# PG03_Schematic_Sheet1.net
KiCad netlist of a schematic drawn in Altium Designer
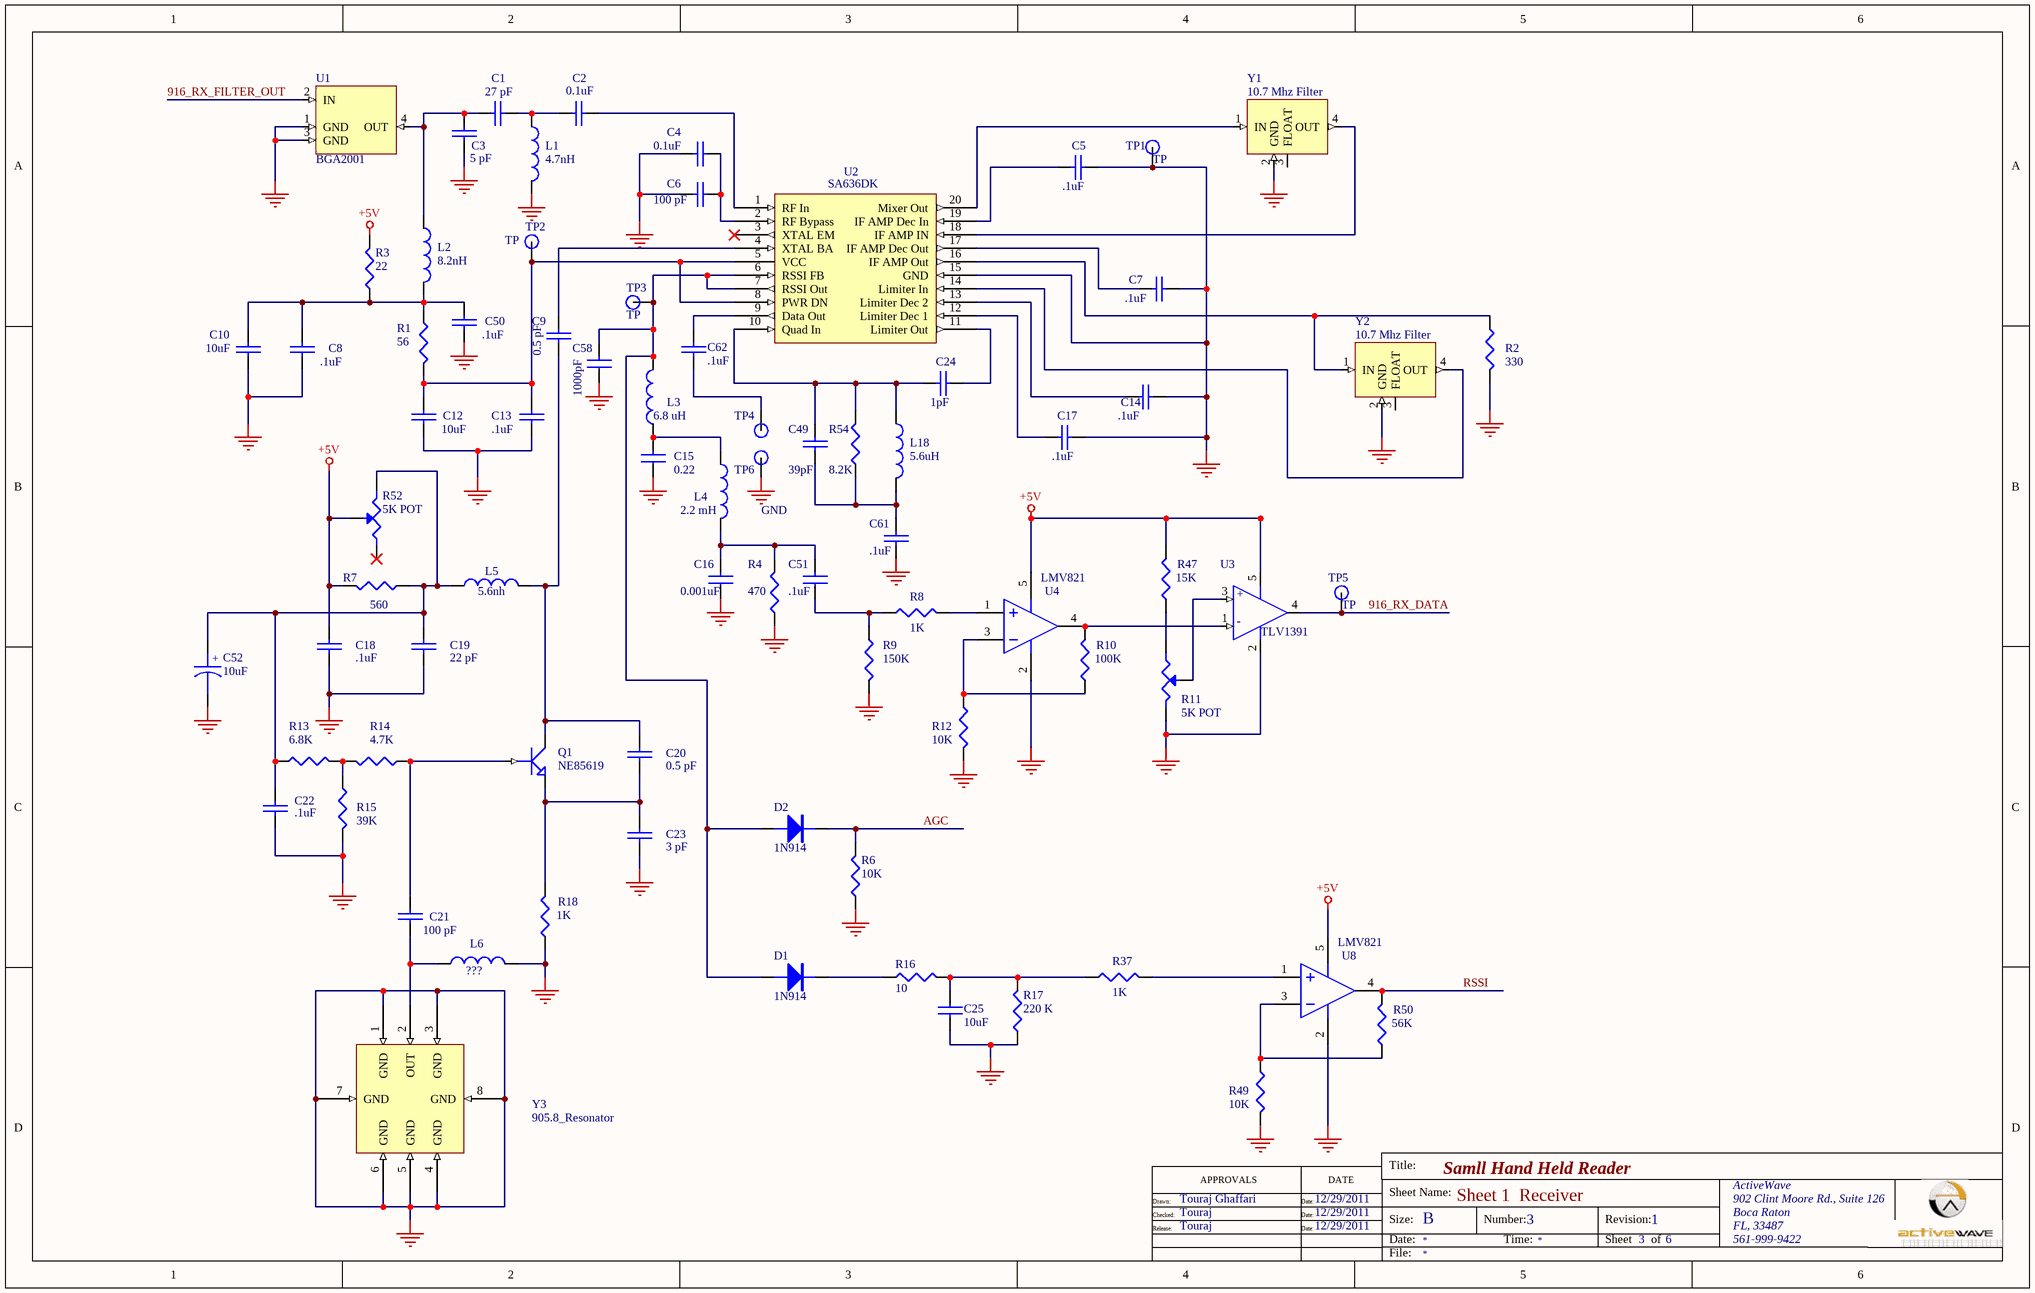
[diagram p0: PG03_Schematic Sheet1.SchDoc]

(export (version "E")
  (design (tool "Eeschema 10.0.6"))
  (components
    (comp (ref "C1")
      (value "27 pF")
      (footprint "0603")
      (description "Capacitor")
      (libsource (lib "*") (part "CAP"))
    )
    (comp (ref "C2")
      (value "0.1uF")
      (footprint "0603")
      (description "Capacitor")
      (libsource (lib "*") (part "CAP"))
    )
    (comp (ref "C3")
      (value "5 pF")
      (footprint "0603")
      (description "Capacitor")
      (libsource (lib "*") (part "CAP"))
    )
    (comp (ref "C4")
      (value "0.1uF")
      (footprint "0603")
      (description "Capacitor")
      (libsource (lib "*") (part "CAP"))
    )
    (comp (ref "C5")
      (value ".1uF")
      (footprint "0603")
      (description "Capacitor")
      (libsource (lib "*") (part "CAP"))
    )
    (comp (ref "C6")
      (value "100 pF")
      (footprint "0603")
      (description "Capacitor")
      (libsource (lib "*") (part "CAP"))
    )
    (comp (ref "C7")
      (value ".1uF")
      (footprint "0603")
      (description "Capacitor")
      (libsource (lib "*") (part "CAP"))
    )
    (comp (ref "C8")
      (value ".1uF")
      (footprint "0603")
      (description "Capacitor")
      (libsource (lib "*") (part "CAP"))
    )
    (comp (ref "C9")
      (value "0.5 pF")
      (footprint "0603")
      (description "Capacitor")
      (libsource (lib "*") (part "CAP"))
    )
    (comp (ref "C10")
      (value "10uF")
      (footprint "CAP A CASE")
      (description "Capacitor")
      (libsource (lib "*") (part "CAP"))
    )
    (comp (ref "C12")
      (value "10uF")
      (footprint "CAP A CASE")
      (description "Capacitor")
      (libsource (lib "*") (part "CAP"))
    )
    (comp (ref "C13")
      (value ".1uF")
      (footprint "0603")
      (description "Capacitor")
      (libsource (lib "*") (part "CAP"))
    )
    (comp (ref "C14")
      (value ".1uF")
      (footprint "0603")
      (description "Capacitor")
      (libsource (lib "*") (part "CAP"))
    )
    (comp (ref "C15") (value "0.22") (footprint "0603") (libsource (lib "*") (part "CAP_NP")))
    (comp (ref "C16") (value "0.001uF") (footprint "0603") (libsource (lib "*") (part "CAP_NP")))
    (comp (ref "C17")
      (value ".1uF")
      (footprint "0603")
      (description "Capacitor")
      (libsource (lib "*") (part "CAP"))
    )
    (comp (ref "C18")
      (value ".1uF")
      (footprint "0603")
      (description "Capacitor")
      (libsource (lib "*") (part "CAP"))
    )
    (comp (ref "C19")
      (value "22 pF")
      (footprint "0603")
      (description "Capacitor")
      (libsource (lib "*") (part "CAP"))
    )
    (comp (ref "C20")
      (value "0.5 pF")
      (footprint "0603")
      (description "Capacitor")
      (libsource (lib "*") (part "CAP"))
    )
    (comp (ref "C21")
      (value "100 pF")
      (footprint "0603")
      (description "Capacitor")
      (libsource (lib "*") (part "CAP"))
    )
    (comp (ref "C22")
      (value ".1uF")
      (footprint "0603")
      (description "Capacitor")
      (libsource (lib "*") (part "CAP"))
    )
    (comp (ref "C23")
      (value "3 pF")
      (footprint "0603")
      (description "Capacitor")
      (libsource (lib "*") (part "CAP"))
    )
    (comp (ref "C24")
      (value "1pF")
      (footprint "0603")
      (description "Capacitor")
      (libsource (lib "*") (part "CAP"))
    )
    (comp (ref "C25") (value "10uF") (footprint "CAP A CASE") (libsource (lib "*") (part "CAP_NP")))
    (comp (ref "C49")
      (value "39pF")
      (footprint "0603")
      (description "Capacitor")
      (libsource (lib "*") (part "CAP"))
    )
    (comp (ref "C50")
      (value ".1uF")
      (footprint "0603")
      (description "Capacitor")
      (libsource (lib "*") (part "CAP"))
    )
    (comp (ref "C51") (value ".1uF") (footprint "0603") (libsource (lib "*") (part "CAP_NP")))
    (comp (ref "C52")
      (value "10uF")
      (footprint "CAP A CASE")
      (description "Capacitor")
      (libsource (lib "*") (part "CAPACITOR POL"))
    )
    (comp (ref "C58") (value "1000pF") (footprint "0603") (libsource (lib "*") (part "CAP_NP")))
    (comp (ref "C61")
      (value ".1uF")
      (footprint "0603")
      (description "Capacitor")
      (libsource (lib "*") (part "CAP"))
    )
    (comp (ref "C62")
      (value ".1uF")
      (footprint "0603")
      (description "Capacitor")
      (libsource (lib "*") (part "CAP"))
    )
    (comp (ref "D1")
      (value "1N914")
      (footprint "SOT23 DIODE")
      (description "Diode")
      (libsource (lib "*") (part "DIODE"))
    )
    (comp (ref "D2")
      (value "1N914")
      (footprint "SOT23 DIODE")
      (description "Diode")
      (libsource (lib "*") (part "DIODE"))
    )
    (comp (ref "L1") (value "4.7nH") (footprint "0603") (libsource (lib "*") (part "INDUCTOR")))
    (comp (ref "L2") (value "8.2nH") (footprint "0603") (libsource (lib "*") (part "INDUCTOR")))
    (comp (ref "L3") (value "6.8 uH") (footprint "0805") (libsource (lib "*") (part "INDUCTOR")))
    (comp (ref "L4") (value "2.2 mH") (footprint "COIL TKS5540CT-ND") (libsource (lib "*") (part "INDUCTOR")))
    (comp (ref "L5") (value "5.6nh") (footprint "0603") (libsource (lib "*") (part "INDUCTOR")))
    (comp (ref "L6") (value "???") (footprint "0603") (libsource (lib "*") (part "INDUCTOR")))
    (comp (ref "L18") (value "5.6uH") (footprint "0603") (libsource (lib "*") (part "INDUCTOR")))
    (comp (ref "Q1")
      (value "NE85619")
      (footprint "3 PIN ULTRA SUPER MINI MOLD")
      (description "NPN Transistor")
      (libsource (lib "*") (part "NPN1"))
    )
    (comp (ref "R1") (value "56") (footprint "0603") (libsource (lib "*") (part "R")))
    (comp (ref "R2") (value "330") (footprint "0603") (libsource (lib "*") (part "R")))
    (comp (ref "R3") (value "22") (footprint "0603") (libsource (lib "*") (part "R")))
    (comp (ref "R4") (value "470") (footprint "0603") (libsource (lib "*") (part "R")))
    (comp (ref "R6") (value "10K") (footprint "0603") (libsource (lib "*") (part "R")))
    (comp (ref "R7") (value "560") (footprint "0603") (libsource (lib "*") (part "RESISTOR")))
    (comp (ref "R8") (value "1K") (footprint "0603") (libsource (lib "*") (part "R")))
    (comp (ref "R9") (value "150K") (footprint "0603") (libsource (lib "*") (part "R")))
    (comp (ref "R10") (value "100K") (footprint "0603") (libsource (lib "*") (part "R")))
    (comp (ref "R11")
      (value "5K POT")
      (footprint "POT PANA EVN5")
      (description "Potentiometer")
      (libsource (lib "*") (part "POT1"))
    )
    (comp (ref "R12") (value "10K") (footprint "0603") (libsource (lib "*") (part "R")))
    (comp (ref "R13") (value "6.8K") (footprint "0603") (libsource (lib "*") (part "RESISTOR")))
    (comp (ref "R14") (value "4.7K") (footprint "0603") (libsource (lib "*") (part "RESISTOR")))
    (comp (ref "R15") (value "39K") (footprint "0603") (libsource (lib "*") (part "RESISTOR")))
    (comp (ref "R16") (value "10") (footprint "0603") (libsource (lib "*") (part "R")))
    (comp (ref "R17") (value "220 K") (footprint "0603") (libsource (lib "*") (part "R")))
    (comp (ref "R18") (value "1K") (footprint "0603") (libsource (lib "*") (part "RESISTOR")))
    (comp (ref "R37") (value "1K") (footprint "0603") (libsource (lib "*") (part "R")))
    (comp (ref "R47") (value "15K") (footprint "0603") (libsource (lib "*") (part "R")))
    (comp (ref "R49") (value "10K") (footprint "0603") (libsource (lib "*") (part "R")))
    (comp (ref "R50") (value "56K") (footprint "0603") (libsource (lib "*") (part "R")))
    (comp (ref "R52")
      (value "5K POT")
      (footprint "POT PANA EVN5")
      (description "Potentiometer")
      (libsource (lib "") (part "POT1_1"))
    )
    (comp (ref "R54") (value "8.2K") (footprint "0603") (libsource (lib "*") (part "R")))
    (comp (ref "TP1") (value "TP") (footprint "TESTPOINT") (libsource (lib "TRX-101R16") (part "TP")))
    (comp (ref "TP2") (value "TP") (footprint "TESTPOINT") (libsource (lib "TRX-101R16") (part "TP")))
    (comp (ref "TP3") (value "TP") (footprint "TESTPOINT") (libsource (lib "TRX-101R16") (part "TP")))
    (comp (ref "TP4") (value "TP") (footprint "TESTPOINT") (libsource (lib "TRX-101R16") (part "TP")))
    (comp (ref "TP5") (value "TP") (footprint "TESTPOINT") (libsource (lib "TRX-101R16") (part "TP")))
    (comp (ref "TP6") (value "GND") (footprint "TESTPOINT") (libsource (lib "TRX-101R16") (part "TP")))
    (comp (ref "U1") (value "BGA2001") (footprint "SOT343") (libsource (lib "*") (part "BGA2001")))
    (comp (ref "U2") (value "SA636DK") (footprint "SSOP20") (libsource (lib "*") (part "SA636DK")))
    (comp (ref "U3") (value "TLV1391") (footprint "SOT25") (libsource (lib "*") (part "TLV1391")))
    (comp (ref "U4") (value "LMV821") (footprint "SOT25") (libsource (lib "*") (part "OPAMP1")))
    (comp (ref "U8") (value "LMV821") (footprint "SOT25") (libsource (lib "*") (part "OPAMP1")))
    (comp (ref "Y1") (value "10.7 Mhz Filter") (footprint "FILTER2") (libsource (lib "*") (part "FILTER2")))
    (comp (ref "Y2") (value "10.7 Mhz Filter") (footprint "FILTER2") (libsource (lib "*") (part "FILTER2")))
    (comp (ref "Y3")
      (value "905.8_Resonator")
      (footprint "RESONATOR")
      (libsource (lib "TRX-101_16") (part "RESONATOR2"))
    )
  )
  (nets
    (net (code "1") (name "+5V") (class "Default")
      (node (ref "C18") (pin "1") (pinfunction "1_1") (pintype "passive"))
      (node (ref "R3") (pin "2") (pinfunction "2_2") (pintype "passive"))
      (node (ref "R47") (pin "2") (pinfunction "2_2") (pintype "passive"))
      (node (ref "R52") (pin "2") (pinfunction "2_2") (pintype "passive"))
      (node (ref "R7") (pin "2") (pinfunction "2_2") (pintype "passive"))
      (node (ref "U3") (pin "5") (pinfunction "VDD_5") (pintype "power_in"))
      (node (ref "U4") (pin "5") (pinfunction "5_5") (pintype "passive"))
      (node (ref "U8") (pin "5") (pinfunction "5_5") (pintype "passive"))
    )
    (net (code "2") (name "/916_RX_DATA") (class "Default")
      (node (ref "TP5") (pin "1") (pinfunction "TP_1") (pintype "passive"))
      (node (ref "U3") (pin "4") (pinfunction "OUT_4") (pintype "open_collector"))
    )
    (net (code "3") (name "/916_RX_FILTER_OUT") (class "Default")
      (node (ref "U1") (pin "2") (pinfunction "IN_2") (pintype "input"))
    )
    (net (code "4") (name "/AGC") (class "Default")
      (node (ref "D2") (pin "K") (pinfunction "K_K") (pintype "passive"))
      (node (ref "R6") (pin "1") (pinfunction "1_1") (pintype "passive"))
    )
    (net (code "5") (name "/RSSI") (class "Default")
      (node (ref "R50") (pin "2") (pinfunction "2_2") (pintype "passive"))
      (node (ref "U8") (pin "4") (pinfunction "4_4") (pintype "passive"))
    )
    (net (code "6") (name "GND_SIGNAL") (class "Default")
      (node (ref "C10") (pin "2") (pinfunction "2_2") (pintype "passive"))
      (node (ref "C12") (pin "2") (pinfunction "2_2") (pintype "passive"))
      (node (ref "C13") (pin "2") (pinfunction "2_2") (pintype "passive"))
      (node (ref "C14") (pin "2") (pinfunction "2_2") (pintype "passive"))
      (node (ref "C15") (pin "1") (pinfunction "1_1") (pintype "passive"))
      (node (ref "C16") (pin "1") (pinfunction "1_1") (pintype "passive"))
      (node (ref "C17") (pin "2") (pinfunction "2_2") (pintype "passive"))
      (node (ref "C18") (pin "2") (pinfunction "2_2") (pintype "passive"))
      (node (ref "C19") (pin "2") (pinfunction "2_2") (pintype "passive"))
      (node (ref "C22") (pin "2") (pinfunction "2_2") (pintype "passive"))
      (node (ref "C23") (pin "2") (pinfunction "2_2") (pintype "passive"))
      (node (ref "C25") (pin "2") (pinfunction "2_2") (pintype "passive"))
      (node (ref "C3") (pin "2") (pinfunction "2_2") (pintype "passive"))
      (node (ref "C4") (pin "1") (pinfunction "1_1") (pintype "passive"))
      (node (ref "C5") (pin "2") (pinfunction "2_2") (pintype "passive"))
      (node (ref "C50") (pin "2") (pinfunction "2_2") (pintype "passive"))
      (node (ref "C52") (pin "2") (pinfunction "2_2") (pintype "passive"))
      (node (ref "C58") (pin "1") (pinfunction "1_1") (pintype "passive"))
      (node (ref "C6") (pin "1") (pinfunction "1_1") (pintype "passive"))
      (node (ref "C61") (pin "2") (pinfunction "2_2") (pintype "passive"))
      (node (ref "C7") (pin "2") (pinfunction "2_2") (pintype "passive"))
      (node (ref "C8") (pin "2") (pinfunction "2_2") (pintype "passive"))
      (node (ref "L1") (pin "2") (pinfunction "2_2") (pintype "passive"))
      (node (ref "L6") (pin "2") (pinfunction "2_2") (pintype "passive"))
      (node (ref "R11") (pin "3") (pinfunction "3_3") (pintype "passive"))
      (node (ref "R12") (pin "2") (pinfunction "2_2") (pintype "passive"))
      (node (ref "R15") (pin "2") (pinfunction "2_2") (pintype "passive"))
      (node (ref "R17") (pin "2") (pinfunction "2_2") (pintype "passive"))
      (node (ref "R18") (pin "1") (pinfunction "1_1") (pintype "passive"))
      (node (ref "R2") (pin "2") (pinfunction "2_2") (pintype "passive"))
      (node (ref "R4") (pin "1") (pinfunction "1_1") (pintype "passive"))
      (node (ref "R49") (pin "2") (pinfunction "2_2") (pintype "passive"))
      (node (ref "R6") (pin "2") (pinfunction "2_2") (pintype "passive"))
      (node (ref "R9") (pin "2") (pinfunction "2_2") (pintype "passive"))
      (node (ref "TP1") (pin "1") (pinfunction "TP_1") (pintype "passive"))
      (node (ref "TP6") (pin "1") (pinfunction "TP_1") (pintype "passive"))
      (node (ref "U1") (pin "1") (pinfunction "GND_1") (pintype "input"))
      (node (ref "U1") (pin "3") (pinfunction "GND_3") (pintype "input"))
      (node (ref "U2") (pin "15") (pinfunction "GND_15") (pintype "input"))
      (node (ref "U3") (pin "2") (pinfunction "VSS_2") (pintype "power_in"))
      (node (ref "U4") (pin "2") (pinfunction "2_2") (pintype "passive"))
      (node (ref "U8") (pin "2") (pinfunction "2_2") (pintype "passive"))
      (node (ref "Y1") (pin "2") (pinfunction "GND_2") (pintype "input"))
      (node (ref "Y2") (pin "2") (pinfunction "GND_2") (pintype "input"))
      (node (ref "Y3") (pin "1") (pinfunction "GND_1") (pintype "input"))
      (node (ref "Y3") (pin "3") (pinfunction "GND_3") (pintype "input"))
      (node (ref "Y3") (pin "4") (pinfunction "GND_4") (pintype "input"))
      (node (ref "Y3") (pin "5") (pinfunction "GND_5") (pintype "input"))
      (node (ref "Y3") (pin "6") (pinfunction "GND_6") (pintype "input"))
      (node (ref "Y3") (pin "7") (pinfunction "GND_7") (pintype "input"))
      (node (ref "Y3") (pin "8") (pinfunction "GND_8") (pintype "input"))
    )
    (net (code "7") (name "Net-(C1-Pad2)") (class "Default")
      (node (ref "C1") (pin "2") (pinfunction "2_2") (pintype "passive"))
      (node (ref "C2") (pin "1") (pinfunction "1_1") (pintype "passive"))
      (node (ref "L1") (pin "1") (pinfunction "1_1") (pintype "passive"))
    )
    (net (code "8") (name "Net-(C10-Pad1)") (class "Default")
      (node (ref "C10") (pin "1") (pinfunction "1_1") (pintype "passive"))
      (node (ref "C50") (pin "1") (pinfunction "1_1") (pintype "passive"))
      (node (ref "C8") (pin "1") (pinfunction "1_1") (pintype "passive"))
      (node (ref "L2") (pin "2") (pinfunction "2_2") (pintype "passive"))
      (node (ref "R1") (pin "1") (pinfunction "1_1") (pintype "passive"))
      (node (ref "R3") (pin "1") (pinfunction "1_1") (pintype "passive"))
    )
    (net (code "9") (name "Net-(C15-Pad2)") (class "Default")
      (node (ref "C15") (pin "2") (pinfunction "2_2") (pintype "passive"))
      (node (ref "L3") (pin "1") (pinfunction "1_1") (pintype "passive"))
      (node (ref "L4") (pin "1") (pinfunction "1_1") (pintype "passive"))
    )
    (net (code "10") (name "Net-(C16-Pad2)") (class "Default")
      (node (ref "C16") (pin "2") (pinfunction "2_2") (pintype "passive"))
      (node (ref "C51") (pin "2") (pinfunction "2_2") (pintype "passive"))
      (node (ref "L4") (pin "2") (pinfunction "2_2") (pintype "passive"))
      (node (ref "R4") (pin "2") (pinfunction "2_2") (pintype "passive"))
    )
    (net (code "11") (name "Net-(C19-Pad1)") (class "Default")
      (node (ref "C19") (pin "1") (pinfunction "1_1") (pintype "passive"))
      (node (ref "C22") (pin "1") (pinfunction "1_1") (pintype "passive"))
      (node (ref "C52") (pin "1") (pinfunction "1_1") (pintype "passive"))
      (node (ref "L5") (pin "1") (pinfunction "1_1") (pintype "passive"))
      (node (ref "R13") (pin "1") (pinfunction "1_1") (pintype "passive"))
      (node (ref "R52") (pin "1") (pinfunction "1_1") (pintype "passive"))
      (node (ref "R7") (pin "1") (pinfunction "1_1") (pintype "passive"))
    )
    (net (code "12") (name "Net-(C20-Pad1)") (class "Default")
      (node (ref "C20") (pin "1") (pinfunction "1_1") (pintype "passive"))
      (node (ref "C9") (pin "1") (pinfunction "1_1") (pintype "passive"))
      (node (ref "L5") (pin "2") (pinfunction "2_2") (pintype "passive"))
      (node (ref "Q1") (pin "C") (pinfunction "C_C") (pintype "passive"))
    )
    (net (code "13") (name "Net-(C20-Pad2)") (class "Default")
      (node (ref "C20") (pin "2") (pinfunction "2_2") (pintype "passive"))
      (node (ref "C23") (pin "1") (pinfunction "1_1") (pintype "passive"))
      (node (ref "Q1") (pin "E") (pinfunction "E_E") (pintype "passive"))
      (node (ref "R18") (pin "2") (pinfunction "2_2") (pintype "passive"))
    )
    (net (code "14") (name "Net-(C21-Pad1)") (class "Default")
      (node (ref "C21") (pin "1") (pinfunction "1_1") (pintype "passive"))
      (node (ref "Q1") (pin "B") (pinfunction "B_B") (pintype "input"))
      (node (ref "R14") (pin "1") (pinfunction "1_1") (pintype "passive"))
    )
    (net (code "15") (name "Net-(C25-Pad1)") (class "Default")
      (node (ref "C25") (pin "1") (pinfunction "1_1") (pintype "passive"))
      (node (ref "R16") (pin "1") (pinfunction "1_1") (pintype "passive"))
      (node (ref "R17") (pin "1") (pinfunction "1_1") (pintype "passive"))
      (node (ref "R37") (pin "1") (pinfunction "1_1") (pintype "passive"))
    )
    (net (code "16") (name "Net-(C49-Pad2)") (class "Default")
      (node (ref "C49") (pin "2") (pinfunction "2_2") (pintype "passive"))
      (node (ref "C61") (pin "1") (pinfunction "1_1") (pintype "passive"))
      (node (ref "L18") (pin "2") (pinfunction "2_2") (pintype "passive"))
      (node (ref "R54") (pin "1") (pinfunction "1_1") (pintype "passive"))
    )
    (net (code "17") (name "Net-(C51-Pad1)") (class "Default")
      (node (ref "C51") (pin "1") (pinfunction "1_1") (pintype "passive"))
      (node (ref "R8") (pin "1") (pinfunction "1_1") (pintype "passive"))
      (node (ref "R9") (pin "1") (pinfunction "1_1") (pintype "passive"))
    )
    (net (code "18") (name "Net-(D1-PadK)") (class "Default")
      (node (ref "D1") (pin "K") (pinfunction "K_K") (pintype "passive"))
      (node (ref "R16") (pin "2") (pinfunction "2_2") (pintype "passive"))
    )
    (net (code "19") (name "Net-(R8-Pad2)") (class "Default")
      (node (ref "R8") (pin "2") (pinfunction "2_2") (pintype "passive"))
      (node (ref "U4") (pin "1") (pinfunction "1_1") (pintype "passive"))
    )
    (net (code "20") (name "Net-(R10-Pad1)") (class "Default")
      (node (ref "R10") (pin "1") (pinfunction "1_1") (pintype "passive"))
      (node (ref "R12") (pin "1") (pinfunction "1_1") (pintype "passive"))
      (node (ref "U4") (pin "3") (pinfunction "3_3") (pintype "passive"))
    )
    (net (code "21") (name "Net-(R11-Pad1)") (class "Default")
      (node (ref "R11") (pin "1") (pinfunction "1_1") (pintype "passive"))
      (node (ref "R47") (pin "1") (pinfunction "1_1") (pintype "passive"))
    )
    (net (code "22") (name "Net-(R13-Pad2)") (class "Default")
      (node (ref "R13") (pin "2") (pinfunction "2_2") (pintype "passive"))
      (node (ref "R14") (pin "2") (pinfunction "2_2") (pintype "passive"))
      (node (ref "R15") (pin "1") (pinfunction "1_1") (pintype "passive"))
    )
    (net (code "23") (name "Net-(R37-Pad2)") (class "Default")
      (node (ref "R37") (pin "2") (pinfunction "2_2") (pintype "passive"))
      (node (ref "U8") (pin "1") (pinfunction "1_1") (pintype "passive"))
    )
    (net (code "24") (name "Net-(R49-Pad1)") (class "Default")
      (node (ref "R49") (pin "1") (pinfunction "1_1") (pintype "passive"))
      (node (ref "R50") (pin "1") (pinfunction "1_1") (pintype "passive"))
      (node (ref "U8") (pin "3") (pinfunction "3_3") (pintype "passive"))
    )
    (net (code "25") (name "Net-(TP2-TP)") (class "Default")
      (node (ref "C12") (pin "1") (pinfunction "1_1") (pintype "passive"))
      (node (ref "C13") (pin "1") (pinfunction "1_1") (pintype "passive"))
      (node (ref "R1") (pin "2") (pinfunction "2_2") (pintype "passive"))
      (node (ref "TP2") (pin "1") (pinfunction "TP_1") (pintype "passive"))
      (node (ref "U2") (pin "5") (pinfunction "VCC_5") (pintype "power_in"))
      (node (ref "U2") (pin "8") (pinfunction "PWR_DN_8") (pintype "input"))
    )
    (net (code "26") (name "Net-(TP3-TP)") (class "Default")
      (node (ref "C58") (pin "2") (pinfunction "2_2") (pintype "passive"))
      (node (ref "D1") (pin "A") (pinfunction "A_A") (pintype "passive"))
      (node (ref "D2") (pin "A") (pinfunction "A_A") (pintype "passive"))
      (node (ref "L3") (pin "2") (pinfunction "2_2") (pintype "passive"))
      (node (ref "TP3") (pin "1") (pinfunction "TP_1") (pintype "passive"))
      (node (ref "U2") (pin "6") (pinfunction "RSSI_FB_6") (pintype "input"))
      (node (ref "U2") (pin "7") (pinfunction "RSSI_Out_7") (pintype "output"))
    )
    (net (code "27") (name "Net-(TP4-TP)") (class "Default")
      (node (ref "C62") (pin "1") (pinfunction "1_1") (pintype "passive"))
      (node (ref "TP4") (pin "1") (pinfunction "TP_1") (pintype "passive"))
    )
    (net (code "28") (name "Net-(U1-OUT)") (class "Default")
      (node (ref "C1") (pin "1") (pinfunction "1_1") (pintype "passive"))
      (node (ref "C3") (pin "1") (pinfunction "1_1") (pintype "passive"))
      (node (ref "L2") (pin "1") (pinfunction "1_1") (pintype "passive"))
      (node (ref "U1") (pin "4") (pinfunction "OUT_4") (pintype "input"))
    )
    (net (code "29") (name "Net-(U2-Data_Out)") (class "Default")
      (node (ref "C62") (pin "2") (pinfunction "2_2") (pintype "passive"))
      (node (ref "U2") (pin "9") (pinfunction "Data_Out_9") (pintype "output"))
    )
    (net (code "30") (name "Net-(U2-IF_AMP_Dec_In)") (class "Default")
      (node (ref "C5") (pin "1") (pinfunction "1_1") (pintype "passive"))
      (node (ref "U2") (pin "19") (pinfunction "IF_AMP_Dec_In_19") (pintype "input"))
    )
    (net (code "31") (name "Net-(U2-IF_AMP_Dec_Out)") (class "Default")
      (node (ref "C7") (pin "1") (pinfunction "1_1") (pintype "passive"))
      (node (ref "U2") (pin "17") (pinfunction "IF_AMP_Dec_Out_17") (pintype "output"))
    )
    (net (code "32") (name "Net-(U2-IF_AMP_IN)") (class "Default")
      (node (ref "U2") (pin "18") (pinfunction "IF_AMP_IN_18") (pintype "input"))
      (node (ref "Y1") (pin "4") (pinfunction "OUT_4") (pintype "output"))
    )
    (net (code "33") (name "Net-(U2-IF_AMP_Out)") (class "Default")
      (node (ref "R2") (pin "1") (pinfunction "1_1") (pintype "passive"))
      (node (ref "U2") (pin "16") (pinfunction "IF_AMP_Out_16") (pintype "output"))
      (node (ref "Y2") (pin "1") (pinfunction "IN_1") (pintype "input"))
    )
    (net (code "34") (name "Net-(U2-Limiter_Dec_1)") (class "Default")
      (node (ref "C17") (pin "1") (pinfunction "1_1") (pintype "passive"))
      (node (ref "U2") (pin "12") (pinfunction "Limiter_Dec_1_12") (pintype "input"))
    )
    (net (code "35") (name "Net-(U2-Limiter_Dec_2)") (class "Default")
      (node (ref "C14") (pin "1") (pinfunction "1_1") (pintype "passive"))
      (node (ref "U2") (pin "13") (pinfunction "Limiter_Dec_2_13") (pintype "input"))
    )
    (net (code "36") (name "Net-(U2-Limiter_In)") (class "Default")
      (node (ref "U2") (pin "14") (pinfunction "Limiter_In_14") (pintype "input"))
      (node (ref "Y2") (pin "4") (pinfunction "OUT_4") (pintype "output"))
    )
    (net (code "37") (name "Net-(U2-Limiter_Out)") (class "Default")
      (node (ref "C24") (pin "2") (pinfunction "2_2") (pintype "passive"))
      (node (ref "U2") (pin "11") (pinfunction "Limiter_Out_11") (pintype "output"))
    )
    (net (code "38") (name "Net-(U2-Mixer_Out)") (class "Default")
      (node (ref "U2") (pin "20") (pinfunction "Mixer_Out_20") (pintype "output"))
      (node (ref "Y1") (pin "1") (pinfunction "IN_1") (pintype "input"))
    )
    (net (code "39") (name "Net-(U2-Quad_In)") (class "Default")
      (node (ref "C24") (pin "1") (pinfunction "1_1") (pintype "passive"))
      (node (ref "C49") (pin "1") (pinfunction "1_1") (pintype "passive"))
      (node (ref "L18") (pin "1") (pinfunction "1_1") (pintype "passive"))
      (node (ref "R54") (pin "2") (pinfunction "2_2") (pintype "passive"))
      (node (ref "U2") (pin "10") (pinfunction "Quad_In_10") (pintype "input"))
    )
    (net (code "40") (name "Net-(U2-RF_Bypass)") (class "Default")
      (node (ref "C4") (pin "2") (pinfunction "2_2") (pintype "passive"))
      (node (ref "C6") (pin "2") (pinfunction "2_2") (pintype "passive"))
      (node (ref "U2") (pin "2") (pinfunction "RF_Bypass_2") (pintype "input"))
    )
    (net (code "41") (name "Net-(U2-RF_In)") (class "Default")
      (node (ref "C2") (pin "2") (pinfunction "2_2") (pintype "passive"))
      (node (ref "U2") (pin "1") (pinfunction "RF_In_1") (pintype "input"))
    )
    (net (code "42") (name "Net-(U2-XTAL_BA)") (class "Default")
      (node (ref "C9") (pin "2") (pinfunction "2_2") (pintype "passive"))
      (node (ref "U2") (pin "4") (pinfunction "XTAL_BA_4") (pintype "input"))
    )
    (net (code "43") (name "Net-(U3-+)") (class "Default")
      (node (ref "R11") (pin "2") (pinfunction "2_2") (pintype "passive"))
      (node (ref "U3") (pin "3") (pinfunction "+_3") (pintype "input"))
    )
    (net (code "44") (name "Net-(U3--)") (class "Default")
      (node (ref "R10") (pin "2") (pinfunction "2_2") (pintype "passive"))
      (node (ref "U3") (pin "1") (pinfunction "-_1") (pintype "input"))
      (node (ref "U4") (pin "4") (pinfunction "4_4") (pintype "passive"))
    )
    (net (code "45") (name "Net-(Y3-OUT)") (class "Default")
      (node (ref "C21") (pin "2") (pinfunction "2_2") (pintype "passive"))
      (node (ref "L6") (pin "1") (pinfunction "1_1") (pintype "passive"))
      (node (ref "Y3") (pin "2") (pinfunction "OUT_2") (pintype "input"))
    )
    (net (code "46") (name "unconnected-(R52-Pad3)") (class "Default")
      (node (ref "R52") (pin "3") (pinfunction "3_3") (pintype "passive+no_connect"))
    )
    (net (code "47") (name "unconnected-(U2-XTAL_EM-Pad3)") (class "Default")
      (node (ref "U2") (pin "3") (pinfunction "XTAL_EM_3") (pintype "output+no_connect"))
    )
    (net (code "48") (name "unconnected-(Y1-FLOAT-Pad3)") (class "Default")
      (node (ref "Y1") (pin "3") (pinfunction "FLOAT_3") (pintype "passive"))
    )
    (net (code "49") (name "unconnected-(Y2-FLOAT-Pad3)") (class "Default")
      (node (ref "Y2") (pin "3") (pinfunction "FLOAT_3") (pintype "passive"))
    )
  )
)
